# OMD_F7_CAN_60V_layout.net
KiCad netlist of a schematic drawn in Altium Designer
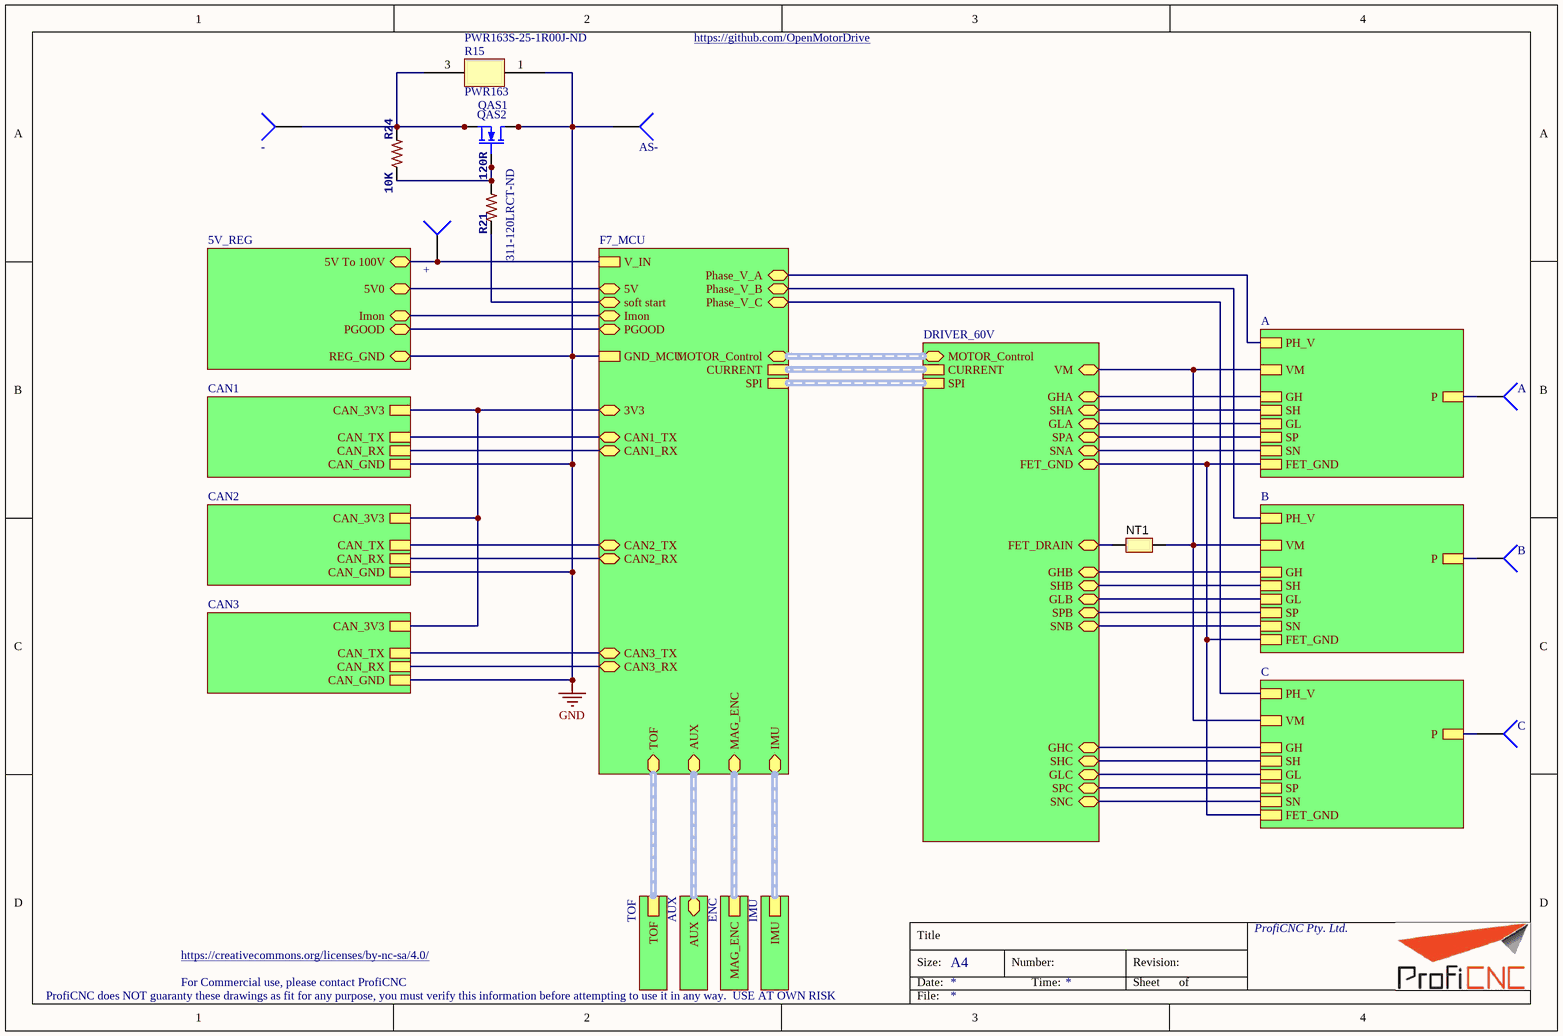
[diagram p0: OMD_F7_CAN_60V_layout.SchDoc]

(export (version "E")
  (design (tool "Eeschema 10.0.6"))
  (components
    (comp (ref "+")
      (value "BATT")
      (footprint "MOTOR_PLUG_F_3.5")
      (description "Socket")
      (libsource (lib "OMD") (part "Socket"))
    )
    (comp (ref "-")
      (value "GND")
      (footprint "MOTOR_PLUG_F_3.5")
      (description "Socket")
      (libsource (lib "OMD") (part "Socket"))
    )
    (comp (ref "A")
      (value "Motor_pad")
      (footprint "MOTOR_PLUG_F_3.5")
      (description "Socket")
      (libsource (lib "OMD") (part "Socket"))
    )
    (comp (ref "AS-")
      (value "GND")
      (footprint "MOTOR_PLUG_F_3.5")
      (description "Socket")
      (libsource (lib "OMD") (part "Socket"))
    )
    (comp (ref "B")
      (value "Motor_pad")
      (footprint "MOTOR_PLUG_F_3.5")
      (description "Socket")
      (libsource (lib "OMD") (part "Socket"))
    )
    (comp (ref "C")
      (value "Motor_pad")
      (footprint "MOTOR_PLUG_F_3.5")
      (description "Socket")
      (libsource (lib "OMD") (part "Socket"))
    )
    (comp (ref "NT1")
      (value "Net-Tie")
      (footprint "Net-Tie_10mil")
      (description "Single point connection between nets.")
      (libsource (lib "OMD") (part "Net-Tie"))
    )
    (comp (ref "QAS1")
      (value "MOSFET-N")
      (footprint "Q5B")
      (description "N-Channel MOSFET")
      (libsource (lib "OMD") (part "MOSFET-N"))
    )
    (comp (ref "QAS2")
      (value "MOSFET-N")
      (footprint "Q5B")
      (description "N-Channel MOSFET")
      (libsource (lib "OMD") (part "MOSFET-N"))
    )
    (comp (ref "R15")
      (value "PWR163")
      (footprint "PWR163")
      (description "The PWR163 Series is a DPAK style surface mount power resistor.")
      (fields (field (name "SUPPLIER PART NUMBER 1") "PWR163S-25-1R00J-ND"))
      (libsource (lib "OMD") (part "Resistor 25W 1R  DPAK"))
    )
    (comp (ref "R21")
      (value "120R")
      (footprint "0402-RES")
      (description "RES 120 OHM 1/16W 1% 0402 SMD")
      (fields (field (name "SUPPLIER PART NUMBER 1") "311-120LRCT-ND"))
      (libsource (lib "altium-import") (part "root_1_RESISTOR0402-RES_"))
    )
    (comp (ref "R24")
      (value "10K")
      (footprint "0402-RES")
      (description "RES 10K OHM 1/16W 1% 0402 SMD")
      (libsource (lib "OMD") (part "RESISTOR0402-RES"))
    )
  )
  (nets
    (net (code "3") (name "/5V To 100V") (class "Default")
      (node (ref "+") (pin "1") (pinfunction "1_1") (pintype "passive"))
    )
    (net (code "12") (name "/FET_DRAIN") (class "Default")
      (node (ref "NT1") (pin "1") (pinfunction "1_1") (pintype "passive"))
    )
    (net (code "24") (name "/P") (class "Default")
      (node (ref "C") (pin "1") (pinfunction "1_1") (pintype "passive"))
    )
    (net (code "29") (name "/P_1") (class "Default")
      (node (ref "A") (pin "1") (pinfunction "1_1") (pintype "passive"))
    )
    (net (code "30") (name "/P_2") (class "Default")
      (node (ref "B") (pin "1") (pinfunction "1_1") (pintype "passive"))
    )
    (net (code "42") (name "/VM") (class "Default")
      (node (ref "NT1") (pin "2") (pinfunction "2_2") (pintype "passive"))
    )
    (net (code "43") (name "/soft start") (class "Default")
      (node (ref "R21") (pin "1") (pinfunction "1_1") (pintype "passive"))
    )
    (net (code "44") (name "GND") (class "Default")
      (node (ref "AS-") (pin "1") (pinfunction "1_1") (pintype "passive"))
      (node (ref "QAS1") (pin "D") (pinfunction "D_D") (pintype "passive"))
      (node (ref "QAS2") (pin "D") (pinfunction "D_D") (pintype "passive"))
      (node (ref "R15") (pin "1") (pintype "passive"))
    )
    (net (code "45") (name "Net-(--Pad1)") (class "Default")
      (node (ref "-") (pin "1") (pinfunction "1_1") (pintype "passive"))
      (node (ref "QAS1") (pin "S") (pinfunction "S_S") (pintype "passive"))
      (node (ref "QAS2") (pin "S") (pinfunction "S_S") (pintype "passive"))
      (node (ref "R15") (pin "3") (pintype "passive"))
      (node (ref "R24") (pin "2") (pinfunction "2_2") (pintype "passive"))
    )
    (net (code "46") (name "Net-(QAS1-PadG)") (class "Default")
      (node (ref "QAS1") (pin "G") (pinfunction "G_G") (pintype "passive"))
      (node (ref "QAS2") (pin "G") (pinfunction "G_G") (pintype "passive"))
      (node (ref "R21") (pin "2") (pinfunction "2_2") (pintype "passive"))
      (node (ref "R24") (pin "1") (pinfunction "1_1") (pintype "passive"))
    )
  )
)
